# uart-usb.net
KiCad netlist of a schematic drawn in EAGLE
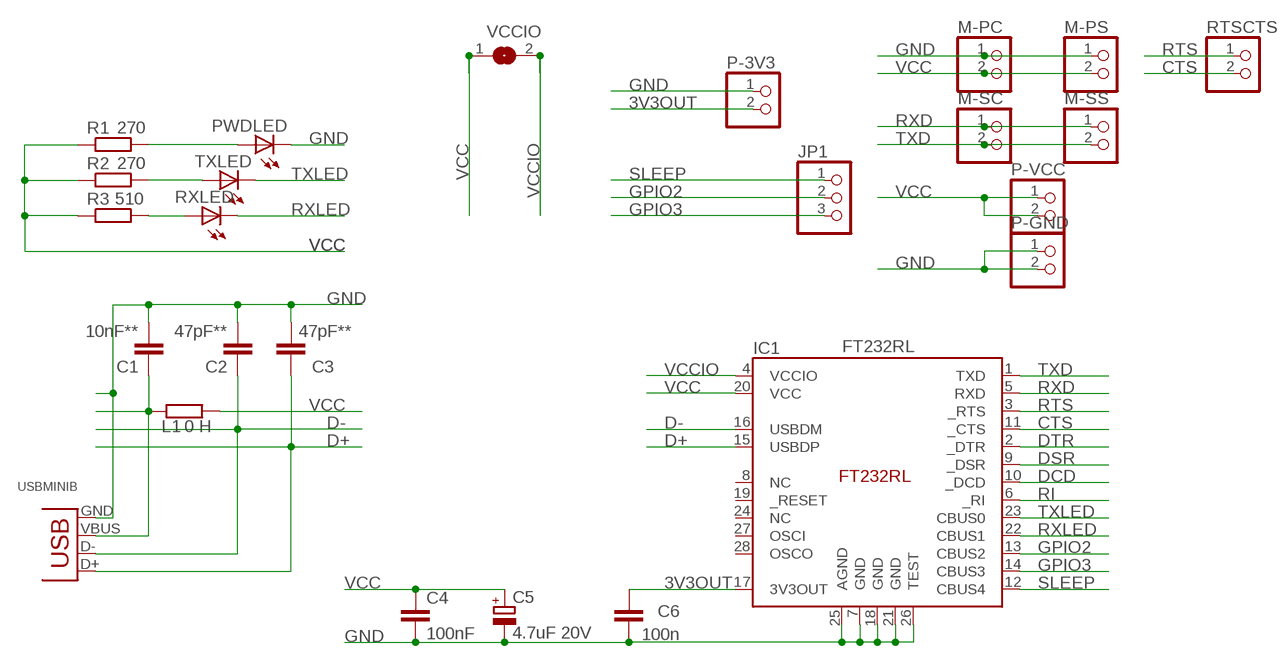
[diagram p0: schematic, sheet 1]

(export (version "E")
  (design (tool "Eeschema 10.0.6"))
  (components
    (comp (ref "C1")
      (value "10nF**")
      (footprint "eagle-import:C0805K")
      (libsource (lib "eagle-import") (part "C-EUC0805K"))
    )
    (comp (ref "C2")
      (value "47pF**")
      (footprint "eagle-import:C0805K")
      (libsource (lib "eagle-import") (part "C-EUC0805K"))
    )
    (comp (ref "C3")
      (value "47pF**")
      (footprint "eagle-import:C0805K")
      (libsource (lib "eagle-import") (part "C-EUC0805K"))
    )
    (comp (ref "C4")
      (value "100nF")
      (footprint "eagle-import:C0805K")
      (libsource (lib "eagle-import") (part "C-EUC0805K"))
    )
    (comp (ref "C5")
      (value "4.7uF 20V")
      (footprint "eagle-import:SMC_A")
      (libsource (lib "eagle-import") (part "CPOL-EUSMCA"))
    )
    (comp (ref "C6")
      (value "100n")
      (footprint "eagle-import:C0805K")
      (libsource (lib "eagle-import") (part "C-EUC0805K"))
    )
    (comp (ref "IC1")
      (value "FT232RL")
      (footprint "eagle-import:SSOP-28")
      (libsource (lib "eagle-import") (part "FT232RL"))
    )
    (comp (ref "JP1")
      (value "PINHD-1X3")
      (footprint "eagle-import:1X03")
      (libsource (lib "eagle-import") (part "PINHD-1X3"))
    )
    (comp (ref "L1")
      (value "0 H")
      (footprint "eagle-import:R0805")
      (libsource (lib "eagle-import") (part "R-EU_R0805"))
    )
    (comp (ref "M-PC")
      (value "PINHD-1X2/90")
      (footprint "eagle-import:1X02_90")
      (libsource (lib "eagle-import") (part "PINHD-1X2/90"))
    )
    (comp (ref "M-PS")
      (value "PINHD-1X2")
      (footprint "eagle-import:1X02")
      (libsource (lib "eagle-import") (part "PINHD-1X2"))
    )
    (comp (ref "M-SC")
      (value "PINHD-1X2/90")
      (footprint "eagle-import:1X02_90")
      (libsource (lib "eagle-import") (part "PINHD-1X2/90"))
    )
    (comp (ref "M-SS")
      (value "PINHD-1X2")
      (footprint "eagle-import:1X02")
      (libsource (lib "eagle-import") (part "PINHD-1X2"))
    )
    (comp (ref "P-3V3")
      (value "PINHD-1X2")
      (footprint "eagle-import:1X02")
      (libsource (lib "eagle-import") (part "PINHD-1X2"))
    )
    (comp (ref "P-GND")
      (value "PINHD-1X2")
      (footprint "eagle-import:1X02")
      (libsource (lib "eagle-import") (part "PINHD-1X2"))
    )
    (comp (ref "P-VCC")
      (value "PINHD-1X2")
      (footprint "eagle-import:1X02")
      (libsource (lib "eagle-import") (part "PINHD-1X2"))
    )
    (comp (ref "PWDLED")
      (value "LEDCHIPLED_0805")
      (footprint "eagle-import:CHIPLED_0805")
      (libsource (lib "eagle-import") (part "LEDCHIPLED_0805"))
    )
    (comp (ref "R1")
      (value "270")
      (footprint "eagle-import:R0805")
      (libsource (lib "eagle-import") (part "R-EU_R0805"))
    )
    (comp (ref "R2")
      (value "270")
      (footprint "eagle-import:R0805")
      (libsource (lib "eagle-import") (part "R-EU_R0805"))
    )
    (comp (ref "R3")
      (value "510")
      (footprint "eagle-import:R0805")
      (libsource (lib "eagle-import") (part "R-EU_R0805"))
    )
    (comp (ref "RTSCTS")
      (value "PINHD-1X2")
      (footprint "eagle-import:1X02")
      (libsource (lib "eagle-import") (part "PINHD-1X2"))
    )
    (comp (ref "RXLED")
      (value "LEDCHIPLED_0805")
      (footprint "eagle-import:CHIPLED_0805")
      (libsource (lib "eagle-import") (part "LEDCHIPLED_0805"))
    )
    (comp (ref "TXLED")
      (value "LEDCHIPLED_0805")
      (footprint "eagle-import:CHIPLED_0805")
      (libsource (lib "eagle-import") (part "LEDCHIPLED_0805"))
    )
    (comp (ref "USBMINIB")
      (value "USB-MB-S")
      (footprint "eagle-import:USB-MB-S")
      (libsource (lib "eagle-import") (part "USB-MB-S"))
    )
    (comp (ref "VCCIO")
      (value "SJ")
      (footprint "eagle-import:SJ")
      (libsource (lib "eagle-import") (part "SJ"))
    )
  )
  (nets
    (net (code "1") (name "/3V3OUT") (class "Default")
      (node (ref "C6") (pin "1") (pinfunction "1_1") (pintype "passive"))
      (node (ref "IC1") (pin "17") (pinfunction "3V3OUT_17") (pintype "output"))
      (node (ref "P-3V3") (pin "2") (pinfunction "2_2") (pintype "passive"))
    )
    (net (code "2") (name "/CTS") (class "Default")
      (node (ref "IC1") (pin "11") (pinfunction "_CTS_11") (pintype "input"))
      (node (ref "RTSCTS") (pin "2") (pinfunction "2_2") (pintype "passive"))
    )
    (net (code "3") (name "/D+") (class "Default")
      (node (ref "C3") (pin "1") (pinfunction "1_1") (pintype "passive"))
      (node (ref "IC1") (pin "15") (pinfunction "USBDP_15") (pintype "bidirectional"))
      (node (ref "USBMINIB") (pin "D+") (pinfunction "D+_D+") (pintype "bidirectional"))
    )
    (net (code "4") (name "/D-") (class "Default")
      (node (ref "C2") (pin "1") (pinfunction "1_1") (pintype "passive"))
      (node (ref "IC1") (pin "16") (pinfunction "USBDM_16") (pintype "bidirectional"))
      (node (ref "USBMINIB") (pin "D-") (pinfunction "D-_D-") (pintype "bidirectional"))
    )
    (net (code "5") (name "/DCD") (class "Default")
      (node (ref "IC1") (pin "10") (pinfunction "_DCD_10") (pintype "input"))
    )
    (net (code "6") (name "/DSR") (class "Default")
      (node (ref "IC1") (pin "9") (pinfunction "_DSR_9") (pintype "input"))
    )
    (net (code "7") (name "/DTR") (class "Default")
      (node (ref "IC1") (pin "2") (pinfunction "_DTR_2") (pintype "input"))
    )
    (net (code "8") (name "/GND") (class "Default")
      (node (ref "C1") (pin "2") (pinfunction "2_2") (pintype "passive"))
      (node (ref "C2") (pin "2") (pinfunction "2_2") (pintype "passive"))
      (node (ref "C3") (pin "2") (pinfunction "2_2") (pintype "passive"))
      (node (ref "C4") (pin "2") (pinfunction "2_2") (pintype "passive"))
      (node (ref "C5") (pin "-") (pinfunction "-_-") (pintype "passive"))
      (node (ref "C6") (pin "2") (pinfunction "2_2") (pintype "passive"))
      (node (ref "IC1") (pin "18") (pinfunction "GND_18") (pintype "power_in"))
      (node (ref "IC1") (pin "21") (pinfunction "GND_21") (pintype "power_in"))
      (node (ref "IC1") (pin "25") (pinfunction "AGND_25") (pintype "power_in"))
      (node (ref "IC1") (pin "26") (pinfunction "TEST_26") (pintype "bidirectional"))
      (node (ref "IC1") (pin "7") (pinfunction "GND_7") (pintype "power_in"))
      (node (ref "M-PC") (pin "1") (pinfunction "1_1") (pintype "passive"))
      (node (ref "M-PS") (pin "1") (pinfunction "1_1") (pintype "passive"))
      (node (ref "P-3V3") (pin "1") (pinfunction "1_1") (pintype "passive"))
      (node (ref "P-GND") (pin "1") (pinfunction "1_1") (pintype "passive"))
      (node (ref "P-GND") (pin "2") (pinfunction "2_2") (pintype "passive"))
      (node (ref "PWDLED") (pin "C") (pinfunction "C_C") (pintype "passive"))
      (node (ref "USBMINIB") (pin "GND") (pinfunction "GND_GND") (pintype "bidirectional"))
    )
    (net (code "9") (name "/GPIO2") (class "Default")
      (node (ref "IC1") (pin "13") (pinfunction "CBUS2_13") (pintype "bidirectional"))
      (node (ref "JP1") (pin "2") (pinfunction "2_2") (pintype "passive"))
    )
    (net (code "10") (name "/GPIO3") (class "Default")
      (node (ref "IC1") (pin "14") (pinfunction "CBUS3_14") (pintype "bidirectional"))
      (node (ref "JP1") (pin "3") (pinfunction "3_3") (pintype "passive"))
    )
    (net (code "11") (name "/RI") (class "Default")
      (node (ref "IC1") (pin "6") (pinfunction "_RI_6") (pintype "input"))
    )
    (net (code "12") (name "/RTS") (class "Default")
      (node (ref "IC1") (pin "3") (pinfunction "_RTS_3") (pintype "output"))
      (node (ref "RTSCTS") (pin "1") (pinfunction "1_1") (pintype "passive"))
    )
    (net (code "13") (name "/RXD") (class "Default")
      (node (ref "IC1") (pin "5") (pinfunction "RXD_5") (pintype "input"))
      (node (ref "M-SC") (pin "1") (pinfunction "1_1") (pintype "passive"))
      (node (ref "M-SS") (pin "1") (pinfunction "1_1") (pintype "passive"))
    )
    (net (code "14") (name "/RXLED") (class "Default")
      (node (ref "IC1") (pin "22") (pinfunction "CBUS1_22") (pintype "bidirectional"))
      (node (ref "RXLED") (pin "C") (pinfunction "C_C") (pintype "passive"))
    )
    (net (code "15") (name "/SLEEP") (class "Default")
      (node (ref "IC1") (pin "12") (pinfunction "CBUS4_12") (pintype "bidirectional"))
      (node (ref "JP1") (pin "1") (pinfunction "1_1") (pintype "passive"))
    )
    (net (code "16") (name "/TXD") (class "Default")
      (node (ref "IC1") (pin "1") (pinfunction "TXD_1") (pintype "output"))
      (node (ref "M-SC") (pin "2") (pinfunction "2_2") (pintype "passive"))
      (node (ref "M-SS") (pin "2") (pinfunction "2_2") (pintype "passive"))
    )
    (net (code "17") (name "/TXLED") (class "Default")
      (node (ref "IC1") (pin "23") (pinfunction "CBUS0_23") (pintype "bidirectional"))
      (node (ref "TXLED") (pin "C") (pinfunction "C_C") (pintype "passive"))
    )
    (net (code "18") (name "/VCC") (class "Default")
      (node (ref "C4") (pin "1") (pinfunction "1_1") (pintype "passive"))
      (node (ref "C5") (pin "+") (pinfunction "+_+") (pintype "passive"))
      (node (ref "IC1") (pin "20") (pinfunction "VCC_20") (pintype "power_in"))
      (node (ref "L1") (pin "2") (pinfunction "2_2") (pintype "passive"))
      (node (ref "M-PC") (pin "2") (pinfunction "2_2") (pintype "passive"))
      (node (ref "M-PS") (pin "2") (pinfunction "2_2") (pintype "passive"))
      (node (ref "P-VCC") (pin "1") (pinfunction "1_1") (pintype "passive"))
      (node (ref "P-VCC") (pin "2") (pinfunction "2_2") (pintype "passive"))
      (node (ref "R1") (pin "1") (pinfunction "1_1") (pintype "passive"))
      (node (ref "R2") (pin "1") (pinfunction "1_1") (pintype "passive"))
      (node (ref "R3") (pin "1") (pinfunction "1_1") (pintype "passive"))
      (node (ref "VCCIO") (pin "1") (pinfunction "1_1") (pintype "passive"))
    )
    (net (code "19") (name "/VCCIO") (class "Default")
      (node (ref "IC1") (pin "4") (pinfunction "VCCIO_4") (pintype "power_in"))
      (node (ref "VCCIO") (pin "2") (pinfunction "2_2") (pintype "passive"))
    )
    (net (code "20") (name "Net-(C1-Pad1)") (class "Default")
      (node (ref "C1") (pin "1") (pinfunction "1_1") (pintype "passive"))
      (node (ref "L1") (pin "1") (pinfunction "1_1") (pintype "passive"))
      (node (ref "USBMINIB") (pin "VBUS") (pinfunction "VBUS_VBUS") (pintype "bidirectional"))
    )
    (net (code "21") (name "Net-(PWDLED-PadA)") (class "Default")
      (node (ref "PWDLED") (pin "A") (pinfunction "A_A") (pintype "passive"))
      (node (ref "R1") (pin "2") (pinfunction "2_2") (pintype "passive"))
    )
    (net (code "22") (name "Net-(R2-Pad2)") (class "Default")
      (node (ref "R2") (pin "2") (pinfunction "2_2") (pintype "passive"))
      (node (ref "TXLED") (pin "A") (pinfunction "A_A") (pintype "passive"))
    )
    (net (code "23") (name "Net-(R3-Pad2)") (class "Default")
      (node (ref "R3") (pin "2") (pinfunction "2_2") (pintype "passive"))
      (node (ref "RXLED") (pin "A") (pinfunction "A_A") (pintype "passive"))
    )
    (net (code "24") (name "unconnected-(IC1-NC-Pad8)") (class "Default")
      (node (ref "IC1") (pin "8") (pinfunction "NC_8") (pintype "no_connect"))
    )
    (net (code "25") (name "unconnected-(IC1-NC-Pad24)") (class "Default")
      (node (ref "IC1") (pin "24") (pinfunction "NC_24") (pintype "no_connect"))
    )
    (net (code "26") (name "unconnected-(IC1-OSCI-Pad27)") (class "Default")
      (node (ref "IC1") (pin "27") (pinfunction "OSCI_27") (pintype "input"))
    )
    (net (code "27") (name "unconnected-(IC1-OSCO-Pad28)") (class "Default")
      (node (ref "IC1") (pin "28") (pinfunction "OSCO_28") (pintype "output"))
    )
    (net (code "28") (name "unconnected-(IC1-_RESET-Pad19)") (class "Default")
      (node (ref "IC1") (pin "19") (pinfunction "_RESET_19") (pintype "input"))
    )
  )
)
